# FPGA.net
KiCad netlist of a schematic drawn in Altium Designer
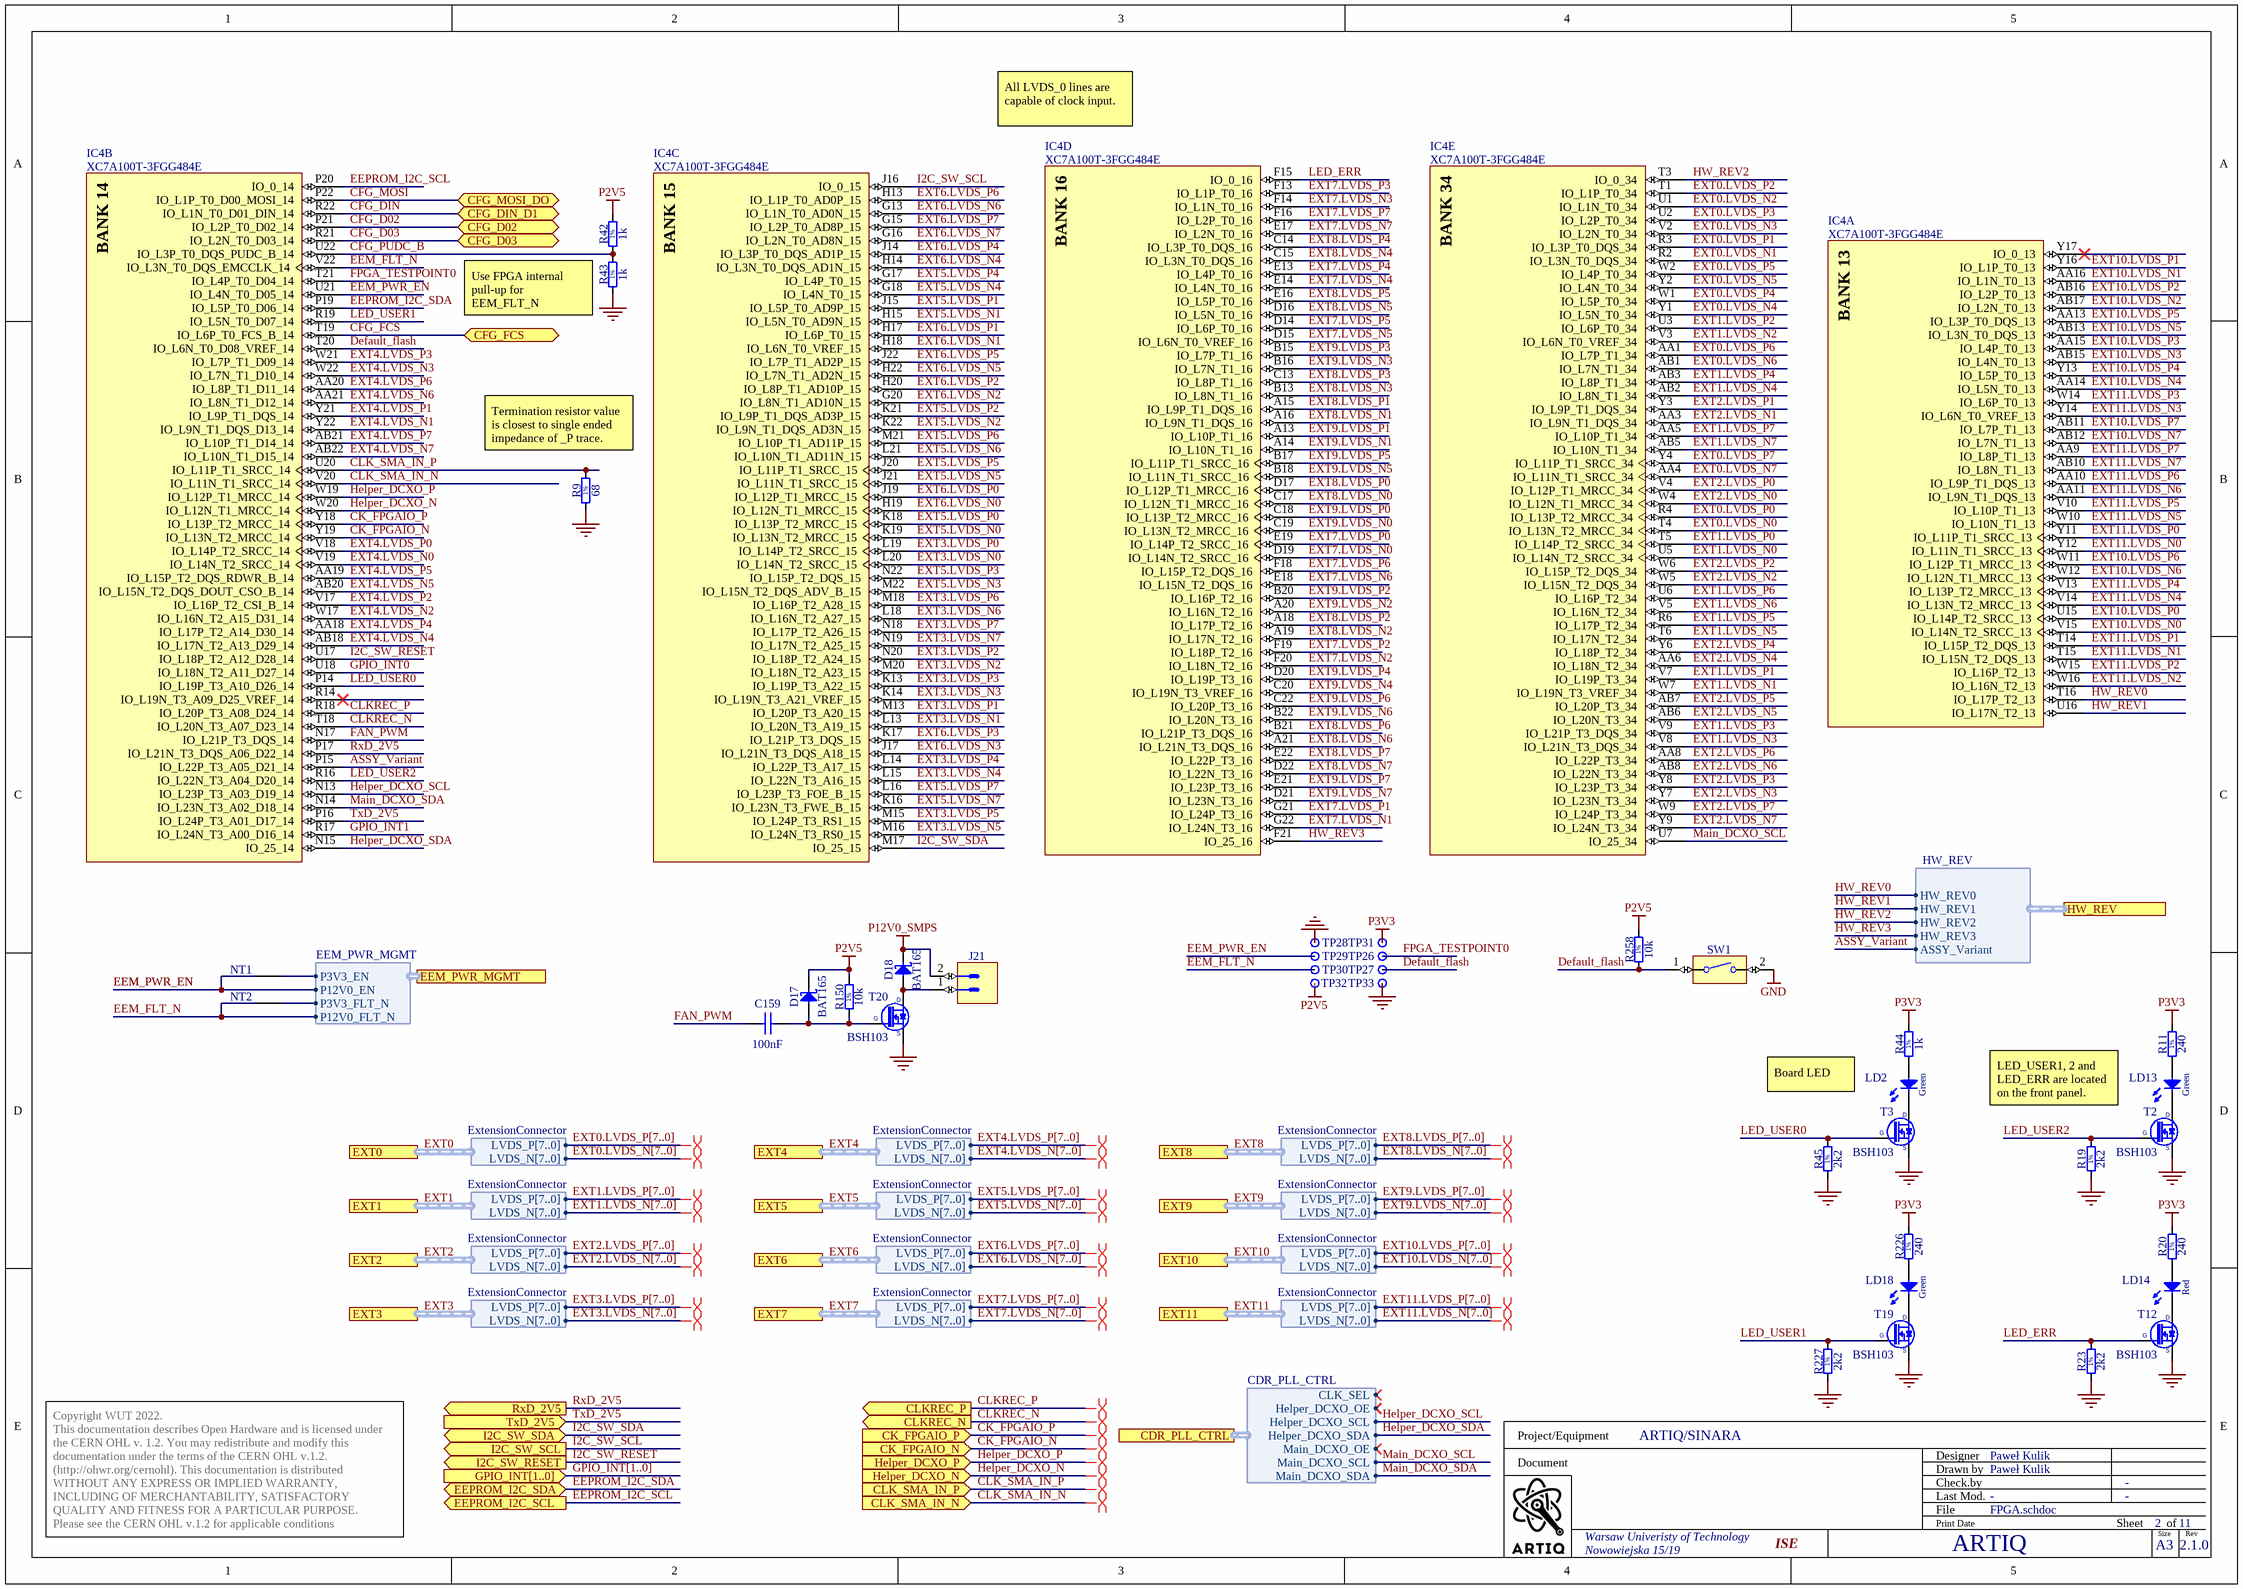
[diagram p0: FPGA.schdoc]

(export (version "E")
  (design (tool "Eeschema 10.0.6"))
  (components
    (comp (ref "C159")
      (value "100nF")
      (footprint "CAPC0603X33N")
      (description "Non-polarised capacitor")
      (fields
        (field (name "PART NUMBER") "CC0201_100NF_6.3V_10%_X5R")
        (field (name "VOLTAGE") "6.3V")
        (field (name "AUTHOR") "CERN DEM JLC")
      )
      (libsource (lib "Capacitors") (part "Capacitor - non polarized"))
    )
    (comp (ref "D17")
      (value "BAT165")
      (footprint "SOD2512X110N")
      (description "Schottky Diode")
      (fields
        (field (name "VOLTAGE") "40V")
        (field (name "POWER") "750mA")
        (field (name "AUTHOR") "CERN DEM JLC")
      )
      (libsource (lib "ICs And Semiconductors") (part "Diode Schottky"))
    )
    (comp (ref "D18")
      (value "BAT165")
      (footprint "SOD2512X110N")
      (description "Schottky Diode")
      (fields
        (field (name "VOLTAGE") "40V")
        (field (name "POWER") "750mA")
        (field (name "AUTHOR") "CERN DEM JLC")
      )
      (libsource (lib "ICs And Semiconductors") (part "Diode Schottky"))
    )
    (comp (ref "IC4")
      (value "XC7A100T-3FGG484E")
      (footprint "BGA484C100P22X22_2300X2300X260")
      (fields (field (name "MANUFACTURER") "XILINX") (field (name "AUTHOR") "CERN DEM BC"))
      (libsource (lib "ICs And Semiconductors") (part "XC7A100T-3FGG484E"))
    )
    (comp (ref "J21")
      (value "KK®")
      (footprint "MOLEX_22-27-2021")
      (description "Connector 2 Male")
      (fields
        (field (name "PART NUMBER") "MOLEX_22-27-2021")
        (field (name "MANUFACTURER") "MOLEX")
        (field (name "AUTHOR") "CERN DEM JLC")
      )
      (libsource (lib "Connectors") (part "Connector 2 Male"))
    )
    (comp (ref "LD2")
      (value "Green")
      (footprint "LED_KINGBRIGHT_KPH-1608CGCK")
      (description "LED Green 1C 2A")
      (fields
        (field (name "MANUFACTURER PART NUMBER") "KPH-1608CGCK")
        (field (name "PART NUMBER") "LED_KINGBRIGHT_KPH-1608CGCK")
        (field (name "AUTHOR") "CERN DEM JLC")
      )
      (libsource (lib "ICs And Semiconductors") (part "LED Green 1C 2A"))
    )
    (comp (ref "LD13")
      (value "Green")
      (footprint "LED_AVAGO_HSME-C120")
      (description "LED Green 1C 2A")
      (fields
        (field (name "MANUFACTURER PART NUMBER") "HSME-C120")
        (field (name "PART NUMBER") "LED_AVAGO_HSME-C120")
        (field (name "AUTHOR") "CERN DEM JMW")
      )
      (libsource (lib "ICs And Semiconductors") (part "LED Green 1C 2A"))
    )
    (comp (ref "LD14")
      (value "Red")
      (footprint "LED_AVAGO_HSMC-C120")
      (description "LED Red 1C 2A")
      (fields
        (field (name "MANUFACTURER PART NUMBER") "HSMC-C120")
        (field (name "PART NUMBER") "LED_AVAGO_HSMC-C120")
        (field (name "AUTHOR") "CERN DEM JMW")
      )
      (libsource (lib "ICs And Semiconductors") (part "LED Red 1C 2A"))
    )
    (comp (ref "LD18")
      (value "Green")
      (footprint "LED_AVAGO_HSME-C120")
      (description "LED Green 1C 2A")
      (fields
        (field (name "MANUFACTURER PART NUMBER") "HSME-C120")
        (field (name "PART NUMBER") "LED_AVAGO_HSME-C120")
        (field (name "AUTHOR") "CERN DEM JMW")
      )
      (libsource (lib "ICs And Semiconductors") (part "LED Green 1C 2A"))
    )
    (comp (ref "NT1")
      (value "Net Tie")
      (footprint "Net Tie")
      (fields (field (name "AUTHOR") "CERN DEM JLC"))
      (libsource (lib "Thermostat") (part "Net Tie"))
    )
    (comp (ref "NT2")
      (value "Net Tie")
      (footprint "Net Tie")
      (fields (field (name "AUTHOR") "CERN DEM JLC"))
      (libsource (lib "Thermostat") (part "Net Tie"))
    )
    (comp (ref "R9")
      (value "68")
      (footprint "RESC1005X40N")
      (description "Resistor - 1%")
      (fields
        (field (name "PART NUMBER") "R0402_68R_1%_0.0625W_100PPM")
        (field (name "POWER") "0.0625W")
        (field (name "AUTHOR") "CERN DEM JLC")
      )
      (libsource (lib "Resistors") (part "Resistor - 1%"))
    )
    (comp (ref "R11")
      (value "240")
      (footprint "RESC1005X40N")
      (description "Resistor - 1%")
      (fields
        (field (name "PART NUMBER") "R0402_240R_1%_0.0625W_100PPM")
        (field (name "POWER") "0.0625W")
        (field (name "AUTHOR") "CERN DEM JLC")
      )
      (libsource (lib "Resistors") (part "Resistor - 1%"))
    )
    (comp (ref "R19")
      (value "2k2")
      (footprint "RESC1005X40N")
      (description "Resistor - 1%")
      (fields
        (field (name "PART NUMBER") "R0402_2K2_1%_0.0625W_100PPM")
        (field (name "POWER") "0.0625W")
        (field (name "AUTHOR") "CERN DEM JLC")
      )
      (libsource (lib "Resistors") (part "Resistor - 1%"))
    )
    (comp (ref "R20")
      (value "240")
      (footprint "RESC1005X40N")
      (description "Resistor - 1%")
      (fields
        (field (name "PART NUMBER") "R0402_240R_1%_0.0625W_100PPM")
        (field (name "POWER") "0.0625W")
        (field (name "AUTHOR") "CERN DEM JLC")
      )
      (libsource (lib "Resistors") (part "Resistor - 1%"))
    )
    (comp (ref "R23")
      (value "2k2")
      (footprint "RESC1005X40N")
      (description "Resistor - 1%")
      (fields
        (field (name "PART NUMBER") "R0402_2K2_1%_0.0625W_100PPM")
        (field (name "POWER") "0.0625W")
        (field (name "AUTHOR") "CERN DEM JLC")
      )
      (libsource (lib "Resistors") (part "Resistor - 1%"))
    )
    (comp (ref "R42")
      (value "1k")
      (footprint "RESC1005X40N")
      (description "Resistor - 1%")
      (fields
        (field (name "PART NUMBER") "R0402_1K_1%_0.0625W_100PPM")
        (field (name "POWER") "0.0625W")
        (field (name "AUTHOR") "CERN DEM JLC")
      )
      (libsource (lib "Resistors") (part "Resistor - 1%"))
    )
    (comp (ref "R43")
      (value "1k")
      (footprint "RESC1005X40N")
      (description "Resistor - 1%")
      (fields
        (field (name "PART NUMBER") "R0402_1K_1%_0.0625W_100PPM")
        (field (name "POWER") "0.0625W")
        (field (name "AUTHOR") "CERN DEM JLC")
      )
      (libsource (lib "Resistors") (part "Resistor - 1%"))
    )
    (comp (ref "R44")
      (value "1k")
      (footprint "RESC1005X40N")
      (description "Resistor - 1%")
      (fields
        (field (name "PART NUMBER") "R0402_1K_1%_0.0625W_100PPM")
        (field (name "POWER") "0.0625W")
        (field (name "AUTHOR") "CERN DEM JLC")
      )
      (libsource (lib "Resistors") (part "Resistor - 1%"))
    )
    (comp (ref "R45")
      (value "2k2")
      (footprint "RESC1005X40N")
      (description "Resistor - 1%")
      (fields
        (field (name "PART NUMBER") "R0402_2K2_1%_0.0625W_100PPM")
        (field (name "POWER") "0.0625W")
        (field (name "AUTHOR") "CERN DEM JLC")
      )
      (libsource (lib "Resistors") (part "Resistor - 1%"))
    )
    (comp (ref "R150")
      (value "10k")
      (footprint "RESC1005X40N")
      (description "Resistor - 1%")
      (fields
        (field (name "PART NUMBER") "R0402_10K_1%_0.0625W_100PPM")
        (field (name "POWER") "0.0625W")
        (field (name "AUTHOR") "CERN DEM JLC")
      )
      (libsource (lib "Resistors") (part "Resistor - 1%"))
    )
    (comp (ref "R226")
      (value "240")
      (footprint "RESC1005X40N")
      (description "Resistor - 1%")
      (fields
        (field (name "PART NUMBER") "R0402_240R_1%_0.0625W_100PPM")
        (field (name "POWER") "0.0625W")
        (field (name "AUTHOR") "CERN DEM JLC")
      )
      (libsource (lib "Resistors") (part "Resistor - 1%"))
    )
    (comp (ref "R227")
      (value "2k2")
      (footprint "RESC1005X40N")
      (description "Resistor - 1%")
      (fields
        (field (name "PART NUMBER") "R0402_2K2_1%_0.0625W_100PPM")
        (field (name "POWER") "0.0625W")
        (field (name "AUTHOR") "CERN DEM JLC")
      )
      (libsource (lib "Resistors") (part "Resistor - 1%"))
    )
    (comp (ref "R258")
      (value "10k")
      (footprint "RESC1005X40N")
      (description "Resistor - 1%")
      (fields
        (field (name "PART NUMBER") "R0402_10K_1%_0.0625W_100PPM")
        (field (name "POWER") "0.0625W")
        (field (name "AUTHOR") "CERN DEM JLC")
      )
      (libsource (lib "Resistors") (part "Resistor - 1%"))
    )
    (comp (ref "SW1")
      (value "Switch")
      (footprint "SW_OMRON_B3U-3000PM")
      (description "1 Ways SPST DIP Switch")
      (fields
        (field (name "PART NUMBER") "SW_OMRON_B3U-3000PM")
        (field (name "MANUFACTURER") "OMRON")
        (field (name "AUTHOR") "CERN DEM HF")
      )
      (libsource (lib "Eletro-mechanical") (part "SW 1x SPST DIP Switch"))
    )
    (comp (ref "T2")
      (value "BSH103")
      (footprint "SOT95P230X110-3N")
      (description "N-CHANNEL MOSFET WITH DIODE")
      (fields (field (name "MANUFACTURER") "NEXPERIA") (field (name "AUTHOR") "CERN DEM JLC"))
      (libsource (lib "ICs And Semiconductors") (part "N-MOSFET-D 1G 2S 3D"))
    )
    (comp (ref "T3")
      (value "BSH103")
      (footprint "SOT95P230X110-3N")
      (description "N-CHANNEL MOSFET WITH DIODE")
      (fields (field (name "MANUFACTURER") "NEXPERIA") (field (name "AUTHOR") "CERN DEM JLC"))
      (libsource (lib "ICs And Semiconductors") (part "N-MOSFET-D 1G 2S 3D"))
    )
    (comp (ref "T12")
      (value "BSH103")
      (footprint "SOT95P230X110-3N")
      (description "N-CHANNEL MOSFET WITH DIODE")
      (fields (field (name "MANUFACTURER") "NEXPERIA") (field (name "AUTHOR") "CERN DEM JLC"))
      (libsource (lib "ICs And Semiconductors") (part "N-MOSFET-D 1G 2S 3D"))
    )
    (comp (ref "T19")
      (value "BSH103")
      (footprint "SOT95P230X110-3N")
      (description "N-CHANNEL MOSFET WITH DIODE")
      (fields (field (name "MANUFACTURER") "NEXPERIA") (field (name "AUTHOR") "CERN DEM JLC"))
      (libsource (lib "ICs And Semiconductors") (part "N-MOSFET-D 1G 2S 3D"))
    )
    (comp (ref "T20")
      (value "BSH103")
      (footprint "SOT95P230X110-3N")
      (description "N-CHANNEL MOSFET WITH DIODE")
      (fields (field (name "MANUFACTURER") "NEXPERIA") (field (name "AUTHOR") "CERN DEM JLC"))
      (libsource (lib "ICs And Semiconductors") (part "N-MOSFET-D 1G 2S 3D"))
    )
    (comp (ref "TP26")
      (value "Plated Hole")
      (footprint "c170h100")
      (description "Single Terminal Socket")
      (fields (field (name "PART NUMBER") "PLATED_HOLE1.0_PAD1.7") (field (name "AUTHOR") "CERN DEM JLC"))
      (libsource (lib "Eletro-mechanical") (part "Single Terminal Socket"))
    )
    (comp (ref "TP27")
      (value "Plated Hole")
      (footprint "c170h100")
      (description "Single Terminal Socket")
      (fields (field (name "PART NUMBER") "PLATED_HOLE1.0_PAD1.7") (field (name "AUTHOR") "CERN DEM JLC"))
      (libsource (lib "Eletro-mechanical") (part "Single Terminal Socket"))
    )
    (comp (ref "TP28")
      (value "Plated Hole")
      (footprint "c170h100")
      (description "Single Terminal Socket")
      (fields (field (name "PART NUMBER") "PLATED_HOLE1.0_PAD1.7") (field (name "AUTHOR") "CERN DEM JLC"))
      (libsource (lib "Eletro-mechanical") (part "Single Terminal Socket"))
    )
    (comp (ref "TP29")
      (value "Plated Hole")
      (footprint "c170h100")
      (description "Single Terminal Socket")
      (fields (field (name "PART NUMBER") "PLATED_HOLE1.0_PAD1.7") (field (name "AUTHOR") "CERN DEM JLC"))
      (libsource (lib "Eletro-mechanical") (part "Single Terminal Socket"))
    )
    (comp (ref "TP30")
      (value "Plated Hole")
      (footprint "c170h100")
      (description "Single Terminal Socket")
      (fields (field (name "PART NUMBER") "PLATED_HOLE1.0_PAD1.7") (field (name "AUTHOR") "CERN DEM JLC"))
      (libsource (lib "Eletro-mechanical") (part "Single Terminal Socket"))
    )
    (comp (ref "TP31")
      (value "Plated Hole")
      (footprint "c170h100")
      (description "Single Terminal Socket")
      (fields (field (name "PART NUMBER") "PLATED_HOLE1.0_PAD1.7") (field (name "AUTHOR") "CERN DEM JLC"))
      (libsource (lib "Eletro-mechanical") (part "Single Terminal Socket"))
    )
    (comp (ref "TP32")
      (value "Plated Hole")
      (footprint "c170h100")
      (description "Single Terminal Socket")
      (fields (field (name "PART NUMBER") "PLATED_HOLE1.0_PAD1.7") (field (name "AUTHOR") "CERN DEM JLC"))
      (libsource (lib "Eletro-mechanical") (part "Single Terminal Socket"))
    )
    (comp (ref "TP33")
      (value "Plated Hole")
      (footprint "c170h100")
      (description "Single Terminal Socket")
      (fields (field (name "PART NUMBER") "PLATED_HOLE1.0_PAD1.7") (field (name "AUTHOR") "CERN DEM JLC"))
      (libsource (lib "Eletro-mechanical") (part "Single Terminal Socket"))
    )
  )
  (nets
    (net (code "16") (name "/ASSY_Variant") (class "Default")
      (node (ref "IC4") (pin "P15") (pinfunction "IO_L22P_T3_A05_D21_14_P15") (pintype "bidirectional"))
    )
    (net (code "17") (name "/CFG_D02") (class "Default")
      (node (ref "IC4") (pin "P21") (pinfunction "IO_L2P_T0_D02_14_P21") (pintype "bidirectional"))
    )
    (net (code "18") (name "/CFG_D03") (class "Default")
      (node (ref "IC4") (pin "R21") (pinfunction "IO_L2N_T0_D03_14_R21") (pintype "bidirectional"))
    )
    (net (code "19") (name "/CFG_DIN") (class "Default")
      (node (ref "IC4") (pin "R22") (pinfunction "IO_L1N_T0_D01_DIN_14_R22") (pintype "bidirectional"))
    )
    (net (code "20") (name "/CFG_FCS") (class "Default")
      (node (ref "IC4") (pin "T19") (pinfunction "IO_L6P_T0_FCS_B_14_T19") (pintype "bidirectional"))
    )
    (net (code "21") (name "/CFG_MOSI") (class "Default")
      (node (ref "IC4") (pin "P22") (pinfunction "IO_L1P_T0_D00_MOSI_14_P22") (pintype "bidirectional"))
    )
    (net (code "22") (name "/CFG_PUDC_B") (class "Default")
      (node (ref "IC4") (pin "U22") (pinfunction "IO_L3P_T0_DQS_PUDC_B_14_U22") (pintype "bidirectional"))
      (node (ref "R42") (pin "1") (pinfunction "1_1") (pintype "passive"))
      (node (ref "R43") (pin "2") (pinfunction "2_2") (pintype "passive"))
    )
    (net (code "23") (name "/CK_FPGAIO_N") (class "Default")
      (node (ref "IC4") (pin "Y19") (pinfunction "IO_L13N_T2_MRCC_14_Y19") (pintype "bidirectional"))
    )
    (net (code "24") (name "/CK_FPGAIO_P") (class "Default")
      (node (ref "IC4") (pin "Y18") (pinfunction "IO_L13P_T2_MRCC_14_Y18") (pintype "bidirectional"))
    )
    (net (code "25") (name "/CLKREC_N") (class "Default")
      (node (ref "IC4") (pin "T18") (pinfunction "IO_L20N_T3_A07_D23_14_T18") (pintype "bidirectional"))
    )
    (net (code "26") (name "/CLKREC_P") (class "Default")
      (node (ref "IC4") (pin "R18") (pinfunction "IO_L20P_T3_A08_D24_14_R18") (pintype "bidirectional"))
    )
    (net (code "27") (name "/CLK_SMA_IN_N") (class "Default")
      (node (ref "IC4") (pin "V20") (pinfunction "IO_L11N_T1_SRCC_14_V20") (pintype "bidirectional"))
    )
    (net (code "28") (name "/CLK_SMA_IN_P") (class "Default")
      (node (ref "IC4") (pin "U20") (pinfunction "IO_L11P_T1_SRCC_14_U20") (pintype "bidirectional"))
      (node (ref "R9") (pin "2") (pinfunction "2_2") (pintype "passive"))
    )
    (net (code "29") (name "/Default_flash") (class "Default")
      (node (ref "IC4") (pin "T20") (pinfunction "IO_L6N_T0_D08_VREF_14_T20") (pintype "bidirectional"))
      (node (ref "R258") (pin "1") (pinfunction "1_1") (pintype "passive"))
      (node (ref "SW1") (pin "1") (pinfunction "1_1") (pintype "bidirectional"))
      (node (ref "TP27") (pin "1") (pinfunction "1_1") (pintype "bidirectional"))
    )
    (net (code "30") (name "/EEM_FLT_N") (class "Default")
      (node (ref "IC4") (pin "V22") (pinfunction "IO_L3N_T0_DQS_EMCCLK_14_V22") (pintype "bidirectional"))
      (node (ref "NT2") (pin "1") (pinfunction "1_1") (pintype "bidirectional"))
      (node (ref "TP30") (pin "1") (pinfunction "1_1") (pintype "bidirectional"))
    )
    (net (code "31") (name "/EEM_PWR_EN") (class "Default")
      (node (ref "IC4") (pin "U21") (pinfunction "IO_L4N_T0_D05_14_U21") (pintype "bidirectional"))
      (node (ref "NT1") (pin "1") (pinfunction "1_1") (pintype "bidirectional"))
      (node (ref "TP29") (pin "1") (pinfunction "1_1") (pintype "bidirectional"))
    )
    (net (code "32") (name "/EEPROM_I2C_SCL") (class "Default")
      (node (ref "IC4") (pin "P20") (pinfunction "IO_0_14_P20") (pintype "bidirectional"))
    )
    (net (code "33") (name "/EEPROM_I2C_SDA") (class "Default")
      (node (ref "IC4") (pin "P19") (pinfunction "IO_L5P_T0_D06_14_P19") (pintype "bidirectional"))
    )
    (net (code "34") (name "/EXT0.LVDS_N0") (class "Default")
      (node (ref "IC4") (pin "T4") (pinfunction "IO_L13N_T2_MRCC_34_T4") (pintype "bidirectional"))
    )
    (net (code "35") (name "/EXT0.LVDS_N1") (class "Default")
      (node (ref "IC4") (pin "R2") (pinfunction "IO_L3N_T0_DQS_34_R2") (pintype "bidirectional"))
    )
    (net (code "36") (name "/EXT0.LVDS_N2") (class "Default")
      (node (ref "IC4") (pin "U1") (pinfunction "IO_L1N_T0_34_U1") (pintype "bidirectional"))
    )
    (net (code "37") (name "/EXT0.LVDS_N3") (class "Default")
      (node (ref "IC4") (pin "V2") (pinfunction "IO_L2N_T0_34_V2") (pintype "bidirectional"))
    )
    (net (code "38") (name "/EXT0.LVDS_N4") (class "Default")
      (node (ref "IC4") (pin "Y1") (pinfunction "IO_L5N_T0_34_Y1") (pintype "bidirectional"))
    )
    (net (code "39") (name "/EXT0.LVDS_N5") (class "Default")
      (node (ref "IC4") (pin "Y2") (pinfunction "IO_L4N_T0_34_Y2") (pintype "bidirectional"))
    )
    (net (code "40") (name "/EXT0.LVDS_N6") (class "Default")
      (node (ref "IC4") (pin "AB1") (pinfunction "IO_L7N_T1_34_AB1") (pintype "bidirectional"))
    )
    (net (code "41") (name "/EXT0.LVDS_N7") (class "Default")
      (node (ref "IC4") (pin "AA4") (pinfunction "IO_L11N_T1_SRCC_34_AA4") (pintype "bidirectional"))
    )
    (net (code "43") (name "/EXT0.LVDS_P0") (class "Default")
      (node (ref "IC4") (pin "R4") (pinfunction "IO_L13P_T2_MRCC_34_R4") (pintype "bidirectional"))
    )
    (net (code "44") (name "/EXT0.LVDS_P1") (class "Default")
      (node (ref "IC4") (pin "R3") (pinfunction "IO_L3P_T0_DQS_34_R3") (pintype "bidirectional"))
    )
    (net (code "45") (name "/EXT0.LVDS_P2") (class "Default")
      (node (ref "IC4") (pin "T1") (pinfunction "IO_L1P_T0_34_T1") (pintype "bidirectional"))
    )
    (net (code "46") (name "/EXT0.LVDS_P3") (class "Default")
      (node (ref "IC4") (pin "U2") (pinfunction "IO_L2P_T0_34_U2") (pintype "bidirectional"))
    )
    (net (code "47") (name "/EXT0.LVDS_P4") (class "Default")
      (node (ref "IC4") (pin "W1") (pinfunction "IO_L5P_T0_34_W1") (pintype "bidirectional"))
    )
    (net (code "48") (name "/EXT0.LVDS_P5") (class "Default")
      (node (ref "IC4") (pin "W2") (pinfunction "IO_L4P_T0_34_W2") (pintype "bidirectional"))
    )
    (net (code "49") (name "/EXT0.LVDS_P6") (class "Default")
      (node (ref "IC4") (pin "AA1") (pinfunction "IO_L7P_T1_34_AA1") (pintype "bidirectional"))
    )
    (net (code "50") (name "/EXT0.LVDS_P7") (class "Default")
      (node (ref "IC4") (pin "Y4") (pinfunction "IO_L11P_T1_SRCC_34_Y4") (pintype "bidirectional"))
    )
    (net (code "51") (name "/EXT1.LVDS_N0") (class "Default")
      (node (ref "IC4") (pin "U5") (pinfunction "IO_L14N_T2_SRCC_34_U5") (pintype "bidirectional"))
    )
    (net (code "52") (name "/EXT1.LVDS_N1") (class "Default")
      (node (ref "IC4") (pin "W7") (pinfunction "IO_L19N_T3_VREF_34_W7") (pintype "bidirectional"))
    )
    (net (code "53") (name "/EXT1.LVDS_N2") (class "Default")
      (node (ref "IC4") (pin "V3") (pinfunction "IO_L6N_T0_VREF_34_V3") (pintype "bidirectional"))
    )
    (net (code "54") (name "/EXT1.LVDS_N3") (class "Default")
      (node (ref "IC4") (pin "V8") (pinfunction "IO_L21N_T3_DQS_34_V8") (pintype "bidirectional"))
    )
    (net (code "55") (name "/EXT1.LVDS_N4") (class "Default")
      (node (ref "IC4") (pin "AB2") (pinfunction "IO_L8N_T1_34_AB2") (pintype "bidirectional"))
    )
    (net (code "56") (name "/EXT1.LVDS_N5") (class "Default")
      (node (ref "IC4") (pin "T6") (pinfunction "IO_L17N_T2_34_T6") (pintype "bidirectional"))
    )
    (net (code "57") (name "/EXT1.LVDS_N6") (class "Default")
      (node (ref "IC4") (pin "V5") (pinfunction "IO_L16N_T2_34_V5") (pintype "bidirectional"))
    )
    (net (code "58") (name "/EXT1.LVDS_N7") (class "Default")
      (node (ref "IC4") (pin "AB5") (pinfunction "IO_L10N_T1_34_AB5") (pintype "bidirectional"))
    )
    (net (code "60") (name "/EXT1.LVDS_P0") (class "Default")
      (node (ref "IC4") (pin "T5") (pinfunction "IO_L14P_T2_SRCC_34_T5") (pintype "bidirectional"))
    )
    (net (code "61") (name "/EXT1.LVDS_P1") (class "Default")
      (node (ref "IC4") (pin "V7") (pinfunction "IO_L19P_T3_34_V7") (pintype "bidirectional"))
    )
    (net (code "62") (name "/EXT1.LVDS_P2") (class "Default")
      (node (ref "IC4") (pin "U3") (pinfunction "IO_L6P_T0_34_U3") (pintype "bidirectional"))
    )
    (net (code "63") (name "/EXT1.LVDS_P3") (class "Default")
      (node (ref "IC4") (pin "V9") (pinfunction "IO_L21P_T3_DQS_34_V9") (pintype "bidirectional"))
    )
    (net (code "64") (name "/EXT1.LVDS_P4") (class "Default")
      (node (ref "IC4") (pin "AB3") (pinfunction "IO_L8P_T1_34_AB3") (pintype "bidirectional"))
    )
    (net (code "65") (name "/EXT1.LVDS_P5") (class "Default")
      (node (ref "IC4") (pin "R6") (pinfunction "IO_L17P_T2_34_R6") (pintype "bidirectional"))
    )
    (net (code "66") (name "/EXT1.LVDS_P6") (class "Default")
      (node (ref "IC4") (pin "U6") (pinfunction "IO_L16P_T2_34_U6") (pintype "bidirectional"))
    )
    (net (code "67") (name "/EXT1.LVDS_P7") (class "Default")
      (node (ref "IC4") (pin "AA5") (pinfunction "IO_L10P_T1_34_AA5") (pintype "bidirectional"))
    )
    (net (code "70") (name "/EXT2.LVDS_N0") (class "Default")
      (node (ref "IC4") (pin "W4") (pinfunction "IO_L12N_T1_MRCC_34_W4") (pintype "bidirectional"))
    )
    (net (code "71") (name "/EXT2.LVDS_N1") (class "Default")
      (node (ref "IC4") (pin "AA3") (pinfunction "IO_L9N_T1_DQS_34_AA3") (pintype "bidirectional"))
    )
    (net (code "72") (name "/EXT2.LVDS_N2") (class "Default")
      (node (ref "IC4") (pin "W5") (pinfunction "IO_L15N_T2_DQS_34_W5") (pintype "bidirectional"))
    )
    (net (code "73") (name "/EXT2.LVDS_N3") (class "Default")
      (node (ref "IC4") (pin "Y7") (pinfunction "IO_L23N_T3_34_Y7") (pintype "bidirectional"))
    )
    (net (code "74") (name "/EXT2.LVDS_N4") (class "Default")
      (node (ref "IC4") (pin "AA6") (pinfunction "IO_L18N_T2_34_AA6") (pintype "bidirectional"))
    )
    (net (code "75") (name "/EXT2.LVDS_N5") (class "Default")
      (node (ref "IC4") (pin "AB6") (pinfunction "IO_L20N_T3_34_AB6") (pintype "bidirectional"))
    )
    (net (code "76") (name "/EXT2.LVDS_N6") (class "Default")
      (node (ref "IC4") (pin "AB8") (pinfunction "IO_L22N_T3_34_AB8") (pintype "bidirectional"))
    )
    (net (code "77") (name "/EXT2.LVDS_N7") (class "Default")
      (node (ref "IC4") (pin "Y9") (pinfunction "IO_L24N_T3_34_Y9") (pintype "bidirectional"))
    )
    (net (code "79") (name "/EXT2.LVDS_P0") (class "Default")
      (node (ref "IC4") (pin "V4") (pinfunction "IO_L12P_T1_MRCC_34_V4") (pintype "bidirectional"))
    )
    (net (code "80") (name "/EXT2.LVDS_P1") (class "Default")
      (node (ref "IC4") (pin "Y3") (pinfunction "IO_L9P_T1_DQS_34_Y3") (pintype "bidirectional"))
    )
    (net (code "81") (name "/EXT2.LVDS_P2") (class "Default")
      (node (ref "IC4") (pin "W6") (pinfunction "IO_L15P_T2_DQS_34_W6") (pintype "bidirectional"))
    )
    (net (code "82") (name "/EXT2.LVDS_P3") (class "Default")
      (node (ref "IC4") (pin "Y8") (pinfunction "IO_L23P_T3_34_Y8") (pintype "bidirectional"))
    )
    (net (code "83") (name "/EXT2.LVDS_P4") (class "Default")
      (node (ref "IC4") (pin "Y6") (pinfunction "IO_L18P_T2_34_Y6") (pintype "bidirectional"))
    )
    (net (code "84") (name "/EXT2.LVDS_P5") (class "Default")
      (node (ref "IC4") (pin "AB7") (pinfunction "IO_L20P_T3_34_AB7") (pintype "bidirectional"))
    )
    (net (code "85") (name "/EXT2.LVDS_P6") (class "Default")
      (node (ref "IC4") (pin "AA8") (pinfunction "IO_L22P_T3_34_AA8") (pintype "bidirectional"))
    )
    (net (code "86") (name "/EXT2.LVDS_P7") (class "Default")
      (node (ref "IC4") (pin "W9") (pinfunction "IO_L24P_T3_34_W9") (pintype "bidirectional"))
    )
    (net (code "87") (name "/EXT3.LVDS_N0") (class "Default")
      (node (ref "IC4") (pin "L20") (pinfunction "IO_L14N_T2_SRCC_15_L20") (pintype "bidirectional"))
    )
    (net (code "88") (name "/EXT3.LVDS_N1") (class "Default")
      (node (ref "IC4") (pin "L13") (pinfunction "IO_L20N_T3_A19_15_L13") (pintype "bidirectional"))
    )
    (net (code "89") (name "/EXT3.LVDS_N2") (class "Default")
      (node (ref "IC4") (pin "M20") (pinfunction "IO_L18N_T2_A23_15_M20") (pintype "bidirectional"))
    )
    (net (code "90") (name "/EXT3.LVDS_N3") (class "Default")
      (node (ref "IC4") (pin "K14") (pinfunction "IO_L19N_T3_A21_VREF_15_K14") (pintype "bidirectional"))
    )
    (net (code "91") (name "/EXT3.LVDS_N4") (class "Default")
      (node (ref "IC4") (pin "L15") (pinfunction "IO_L22N_T3_A16_15_L15") (pintype "bidirectional"))
    )
    (net (code "92") (name "/EXT3.LVDS_N5") (class "Default")
      (node (ref "IC4") (pin "M16") (pinfunction "IO_L24N_T3_RS0_15_M16") (pintype "bidirectional"))
    )
    (net (code "93") (name "/EXT3.LVDS_N6") (class "Default")
      (node (ref "IC4") (pin "L18") (pinfunction "IO_L16N_T2_A27_15_L18") (pintype "bidirectional"))
    )
    (net (code "94") (name "/EXT3.LVDS_N7") (class "Default")
      (node (ref "IC4") (pin "N19") (pinfunction "IO_L17N_T2_A25_15_N19") (pintype "bidirectional"))
    )
    (net (code "96") (name "/EXT3.LVDS_P0") (class "Default")
      (node (ref "IC4") (pin "L19") (pinfunction "IO_L14P_T2_SRCC_15_L19") (pintype "bidirectional"))
    )
    (net (code "97") (name "/EXT3.LVDS_P1") (class "Default")
      (node (ref "IC4") (pin "M13") (pinfunction "IO_L20P_T3_A20_15_M13") (pintype "bidirectional"))
    )
    (net (code "98") (name "/EXT3.LVDS_P2") (class "Default")
      (node (ref "IC4") (pin "N20") (pinfunction "IO_L18P_T2_A24_15_N20") (pintype "bidirectional"))
    )
    (net (code "99") (name "/EXT3.LVDS_P3") (class "Default")
      (node (ref "IC4") (pin "K13") (pinfunction "IO_L19P_T3_A22_15_K13") (pintype "bidirectional"))
    )
    (net (code "100") (name "/EXT3.LVDS_P4") (class "Default")
      (node (ref "IC4") (pin "L14") (pinfunction "IO_L22P_T3_A17_15_L14") (pintype "bidirectional"))
    )
    (net (code "101") (name "/EXT3.LVDS_P5") (class "Default")
      (node (ref "IC4") (pin "M15") (pinfunction "IO_L24P_T3_RS1_15_M15") (pintype "bidirectional"))
    )
    (net (code "102") (name "/EXT3.LVDS_P6") (class "Default")
      (node (ref "IC4") (pin "M18") (pinfunction "IO_L16P_T2_A28_15_M18") (pintype "bidirectional"))
    )
    (net (code "103") (name "/EXT3.LVDS_P7") (class "Default")
      (node (ref "IC4") (pin "N18") (pinfunction "IO_L17P_T2_A26_15_N18") (pintype "bidirectional"))
    )
    (net (code "104") (name "/EXT4.LVDS_N0") (class "Default")
      (node (ref "IC4") (pin "V19") (pinfunction "IO_L14N_T2_SRCC_14_V19") (pintype "bidirectional"))
    )
    (net (code "105") (name "/EXT4.LVDS_N1") (class "Default")
      (node (ref "IC4") (pin "Y22") (pinfunction "IO_L9N_T1_DQS_D13_14_Y22") (pintype "bidirectional"))
    )
    (net (code "106") (name "/EXT4.LVDS_N2") (class "Default")
      (node (ref "IC4") (pin "W17") (pinfunction "IO_L16N_T2_A15_D31_14_W17") (pintype "bidirectional"))
    )
    (net (code "107") (name "/EXT4.LVDS_N3") (class "Default")
      (node (ref "IC4") (pin "W22") (pinfunction "IO_L7N_T1_D10_14_W22") (pintype "bidirectional"))
    )
    (net (code "108") (name "/EXT4.LVDS_N4") (class "Default")
      (node (ref "IC4") (pin "AB18") (pinfunction "IO_L17N_T2_A13_D29_14_AB18") (pintype "bidirectional"))
    )
    (net (code "109") (name "/EXT4.LVDS_N5") (class "Default")
      (node (ref "IC4") (pin "AB20") (pinfunction "IO_L15N_T2_DQS_DOUT_CSO_B_14_AB20") (pintype "bidirectional"))
    )
    (net (code "110") (name "/EXT4.LVDS_N6") (class "Default")
      (node (ref "IC4") (pin "AA21") (pinfunction "IO_L8N_T1_D12_14_AA21") (pintype "bidirectional"))
    )
    (net (code "111") (name "/EXT4.LVDS_N7") (class "Default")
      (node (ref "IC4") (pin "AB22") (pinfunction "IO_L10N_T1_D15_14_AB22") (pintype "bidirectional"))
    )
    (net (code "113") (name "/EXT4.LVDS_P0") (class "Default")
      (node (ref "IC4") (pin "V18") (pinfunction "IO_L14P_T2_SRCC_14_V18") (pintype "bidirectional"))
    )
    (net (code "114") (name "/EXT4.LVDS_P1") (class "Default")
      (node (ref "IC4") (pin "Y21") (pinfunction "IO_L9P_T1_DQS_14_Y21") (pintype "bidirectional"))
    )
    (net (code "115") (name "/EXT4.LVDS_P2") (class "Default")
      (node (ref "IC4") (pin "V17") (pinfunction "IO_L16P_T2_CSI_B_14_V17") (pintype "bidirectional"))
    )
    (net (code "116") (name "/EXT4.LVDS_P3") (class "Default")
      (node (ref "IC4") (pin "W21") (pinfunction "IO_L7P_T1_D09_14_W21") (pintype "bidirectional"))
    )
    (net (code "117") (name "/EXT4.LVDS_P4") (class "Default")
      (node (ref "IC4") (pin "AA18") (pinfunction "IO_L17P_T2_A14_D30_14_AA18") (pintype "bidirectional"))
    )
    (net (code "118") (name "/EXT4.LVDS_P5") (class "Default")
      (node (ref "IC4") (pin "AA19") (pinfunction "IO_L15P_T2_DQS_RDWR_B_14_AA19") (pintype "bidirectional"))
    )
    (net (code "119") (name "/EXT4.LVDS_P6") (class "Default")
      (node (ref "IC4") (pin "AA20") (pinfunction "IO_L8P_T1_D11_14_AA20") (pintype "bidirectional"))
    )
    (net (code "120") (name "/EXT4.LVDS_P7") (class "Default")
      (node (ref "IC4") (pin "AB21") (pinfunction "IO_L10P_T1_D14_14_AB21") (pintype "bidirectional"))
    )
    (net (code "121") (name "/EXT5.LVDS_N0") (class "Default")
      (node (ref "IC4") (pin "K19") (pinfunction "IO_L13N_T2_MRCC_15_K19") (pintype "bidirectional"))
    )
    (net (code "122") (name "/EXT5.LVDS_N1") (class "Default")
      (node (ref "IC4") (pin "H15") (pinfunction "IO_L5N_T0_AD9N_15_H15") (pintype "bidirectional"))
    )
    (net (code "123") (name "/EXT5.LVDS_N2") (class "Default")
      (node (ref "IC4") (pin "K22") (pinfunction "IO_L9N_T1_DQS_AD3N_15_K22") (pintype "bidirectional"))
    )
    (net (code "124") (name "/EXT5.LVDS_N3") (class "Default")
      (node (ref "IC4") (pin "M22") (pinfunction "IO_L15N_T2_DQS_ADV_B_15_M22") (pintype "bidirectional"))
    )
    (net (code "125") (name "/EXT5.LVDS_N4") (class "Default")
      (node (ref "IC4") (pin "G18") (pinfunction "IO_L4N_T0_15_G18") (pintype "bidirectional"))
    )
    (net (code "126") (name "/EXT5.LVDS_N5") (class "Default")
      (node (ref "IC4") (pin "J21") (pinfunction "IO_L11N_T1_SRCC_15_J21") (pintype "bidirectional"))
    )
    (net (code "127") (name "/EXT5.LVDS_N6") (class "Default")
      (node (ref "IC4") (pin "L21") (pinfunction "IO_L10N_T1_AD11N_15_L21") (pintype "bidirectional"))
    )
    (net (code "128") (name "/EXT5.LVDS_N7") (class "Default")
      (node (ref "IC4") (pin "K16") (pinfunction "IO_L23N_T3_FWE_B_15_K16") (pintype "bidirectional"))
    )
    (net (code "130") (name "/EXT5.LVDS_P0") (class "Default")
      (node (ref "IC4") (pin "K18") (pinfunction "IO_L13P_T2_MRCC_15_K18") (pintype "bidirectional"))
    )
    (net (code "131") (name "/EXT5.LVDS_P1") (class "Default")
      (node (ref "IC4") (pin "J15") (pinfunction "IO_L5P_T0_AD9P_15_J15") (pintype "bidirectional"))
    )
    (net (code "132") (name "/EXT5.LVDS_P2") (class "Default")
      (node (ref "IC4") (pin "K21") (pinfunction "IO_L9P_T1_DQS_AD3P_15_K21") (pintype "bidirectional"))
    )
    (net (code "133") (name "/EXT5.LVDS_P3") (class "Default")
      (node (ref "IC4") (pin "N22") (pinfunction "IO_L15P_T2_DQS_15_N22") (pintype "bidirectional"))
    )
    (net (code "134") (name "/EXT5.LVDS_P4") (class "Default")
      (node (ref "IC4") (pin "G17") (pinfunction "IO_L4P_T0_15_G17") (pintype "bidirectional"))
    )
    (net (code "135") (name "/EXT5.LVDS_P5") (class "Default")
      (node (ref "IC4") (pin "J20") (pinfunction "IO_L11P_T1_SRCC_15_J20") (pintype "bidirectional"))
    )
    (net (code "136") (name "/EXT5.LVDS_P6") (class "Default")
      (node (ref "IC4") (pin "M21") (pinfunction "IO_L10P_T1_AD11P_15_M21") (pintype "bidirectional"))
    )
    (net (code "137") (name "/EXT5.LVDS_P7") (class "Default")
      (node (ref "IC4") (pin "L16") (pinfunction "IO_L23P_T3_FOE_B_15_L16") (pintype "bidirectional"))
    )
    (net (code "140") (name "/EXT6.LVDS_N0") (class "Default")
      (node (ref "IC4") (pin "H19") (pinfunction "IO_L12N_T1_MRCC_15_H19") (pintype "bidirectional"))
    )
    (net (code "141") (name "/EXT6.LVDS_N1") (class "Default")
      (node (ref "IC4") (pin "H18") (pinfunction "IO_L6N_T0_VREF_15_H18") (pintype "bidirectional"))
    )
    (net (code "142") (name "/EXT6.LVDS_N2") (class "Default")
      (node (ref "IC4") (pin "G20") (pinfunction "IO_L8N_T1_AD10N_15_G20") (pintype "bidirectional"))
    )
    (net (code "143") (name "/EXT6.LVDS_N3") (class "Default")
      (node (ref "IC4") (pin "J17") (pinfunction "IO_L21N_T3_DQS_A18_15_J17") (pintype "bidirectional"))
    )
    (net (code "144") (name "/EXT6.LVDS_N4") (class "Default")
      (node (ref "IC4") (pin "H14") (pinfunction "IO_L3N_T0_DQS_AD1N_15_H14") (pintype "bidirectional"))
    )
    (net (code "145") (name "/EXT6.LVDS_N5") (class "Default")
      (node (ref "IC4") (pin "H22") (pinfunction "IO_L7N_T1_AD2N_15_H22") (pintype "bidirectional"))
    )
    (net (code "146") (name "/EXT6.LVDS_N6") (class "Default")
      (node (ref "IC4") (pin "G13") (pinfunction "IO_L1N_T0_AD0N_15_G13") (pintype "bidirectional"))
    )
    (net (code "147") (name "/EXT6.LVDS_N7") (class "Default")
      (node (ref "IC4") (pin "G16") (pinfunction "IO_L2N_T0_AD8N_15_G16") (pintype "bidirectional"))
    )
    (net (code "149") (name "/EXT6.LVDS_P0") (class "Default")
      (node (ref "IC4") (pin "J19") (pinfunction "IO_L12P_T1_MRCC_15_J19") (pintype "bidirectional"))
    )
    (net (code "150") (name "/EXT6.LVDS_P1") (class "Default")
      (node (ref "IC4") (pin "H17") (pinfunction "IO_L6P_T0_15_H17") (pintype "bidirectional"))
    )
    (net (code "151") (name "/EXT6.LVDS_P2") (class "Default")
      (node (ref "IC4") (pin "H20") (pinfunction "IO_L8P_T1_AD10P_15_H20") (pintype "bidirectional"))
    )
    (net (code "152") (name "/EXT6.LVDS_P3") (class "Default")
      (node (ref "IC4") (pin "K17") (pinfunction "IO_L21P_T3_DQS_15_K17") (pintype "bidirectional"))
    )
    (net (code "153") (name "/EXT6.LVDS_P4") (class "Default")
      (node (ref "IC4") (pin "J14") (pinfunction "IO_L3P_T0_DQS_AD1P_15_J14") (pintype "bidirectional"))
    )
    (net (code "154") (name "/EXT6.LVDS_P5") (class "Default")
      (node (ref "IC4") (pin "J22") (pinfunction "IO_L7P_T1_AD2P_15_J22") (pintype "bidirectional"))
    )
    (net (code "155") (name "/EXT6.LVDS_P6") (class "Default")
      (node (ref "IC4") (pin "H13") (pinfunction "IO_L1P_T0_AD0P_15_H13") (pintype "bidirectional"))
    )
    (net (code "156") (name "/EXT6.LVDS_P7") (class "Default")
      (node (ref "IC4") (pin "G15") (pinfunction "IO_L2P_T0_AD8P_15_G15") (pintype "bidirectional"))
    )
    (net (code "159") (name "/EXT7.LVDS_N0") (class "Default")
      (node (ref "IC4") (pin "D19") (pinfunction "IO_L14N_T2_SRCC_16_D19") (pintype "bidirectional"))
    )
    (net (code "160") (name "/EXT7.LVDS_N1") (class "Default")
      (node (ref "IC4") (pin "G22") (pinfunction "IO_L24N_T3_16_G22") (pintype "bidirectional"))
    )
    (net (code "161") (name "/EXT7.LVDS_N2") (class "Default")
      (node (ref "IC4") (pin "F20") (pinfunction "IO_L18N_T2_16_F20") (pintype "bidirectional"))
    )
    (net (code "162") (name "/EXT7.LVDS_N3") (class "Default")
      (node (ref "IC4") (pin "F14") (pinfunction "IO_L1N_T0_16_F14") (pintype "bidirectional"))
    )
    (net (code "163") (name "/EXT7.LVDS_N4") (class "Default")
      (node (ref "IC4") (pin "E14") (pinfunction "IO_L4N_T0_16_E14") (pintype "bidirectional"))
    )
    (net (code "164") (name "/EXT7.LVDS_N5") (class "Default")
      (node (ref "IC4") (pin "D15") (pinfunction "IO_L6N_T0_VREF_16_D15") (pintype "bidirectional"))
    )
    (net (code "165") (name "/EXT7.LVDS_N6") (class "Default")
      (node (ref "IC4") (pin "E18") (pinfunction "IO_L15N_T2_DQS_16_E18") (pintype "bidirectional"))
    )
    (net (code "166") (name "/EXT7.LVDS_N7") (class "Default")
      (node (ref "IC4") (pin "E17") (pinfunction "IO_L2N_T0_16_E17") (pintype "bidirectional"))
    )
    (net (code "168") (name "/EXT7.LVDS_P0") (class "Default")
      (node (ref "IC4") (pin "E19") (pinfunction "IO_L14P_T2_SRCC_16_E19") (pintype "bidirectional"))
    )
    (net (code "169") (name "/EXT7.LVDS_P1") (class "Default")
      (node (ref "IC4") (pin "G21") (pinfunction "IO_L24P_T3_16_G21") (pintype "bidirectional"))
    )
    (net (code "170") (name "/EXT7.LVDS_P2") (class "Default")
      (node (ref "IC4") (pin "F19") (pinfunction "IO_L18P_T2_16_F19") (pintype "bidirectional"))
    )
    (net (code "171") (name "/EXT7.LVDS_P3") (class "Default")
      (node (ref "IC4") (pin "F13") (pinfunction "IO_L1P_T0_16_F13") (pintype "bidirectional"))
    )
    (net (code "172") (name "/EXT7.LVDS_P4") (class "Default")
      (node (ref "IC4") (pin "E13") (pinfunction "IO_L4P_T0_16_E13") (pintype "bidirectional"))
    )
    (net (code "173") (name "/EXT7.LVDS_P5") (class "Default")
      (node (ref "IC4") (pin "D14") (pinfunction "IO_L6P_T0_16_D14") (pintype "bidirectional"))
    )
    (net (code "174") (name "/EXT7.LVDS_P6") (class "Default")
      (node (ref "IC4") (pin "F18") (pinfunction "IO_L15P_T2_DQS_16_F18") (pintype "bidirectional"))
    )
    (net (code "175") (name "/EXT7.LVDS_P7") (class "Default")
      (node (ref "IC4") (pin "F16") (pinfunction "IO_L2P_T0_16_F16") (pintype "bidirectional"))
    )
    (net (code "178") (name "/EXT8.LVDS_N0") (class "Default")
      (node (ref "IC4") (pin "C17") (pinfunction "IO_L12N_T1_MRCC_16_C17") (pintype "bidirectional"))
    )
    (net (code "179") (name "/EXT8.LVDS_N1") (class "Default")
      (node (ref "IC4") (pin "A16") (pinfunction "IO_L9N_T1_DQS_16_A16") (pintype "bidirectional"))
    )
    (net (code "180") (name "/EXT8.LVDS_N2") (class "Default")
      (node (ref "IC4") (pin "A19") (pinfunction "IO_L17N_T2_16_A19") (pintype "bidirectional"))
    )
    (net (code "181") (name "/EXT8.LVDS_N3") (class "Default")
      (node (ref "IC4") (pin "B13") (pinfunction "IO_L8N_T1_16_B13") (pintype "bidirectional"))
    )
    (net (code "182") (name "/EXT8.LVDS_N4") (class "Default")
      (node (ref "IC4") (pin "C15") (pinfunction "IO_L3N_T0_DQS_16_C15") (pintype "bidirectional"))
    )
    (net (code "183") (name "/EXT8.LVDS_N5") (class "Default")
      (node (ref "IC4") (pin "D16") (pinfunction "IO_L5N_T0_16_D16") (pintype "bidirectional"))
    )
    (net (code "184") (name "/EXT8.LVDS_N6") (class "Default")
      (node (ref "IC4") (pin "A21") (pinfunction "IO_L21N_T3_DQS_16_A21") (pintype "bidirectional"))
    )
    (net (code "185") (name "/EXT8.LVDS_N7") (class "Default")
      (node (ref "IC4") (pin "D22") (pinfunction "IO_L22N_T3_16_D22") (pintype "bidirectional"))
    )
    (net (code "187") (name "/EXT8.LVDS_P0") (class "Default")
      (node (ref "IC4") (pin "D17") (pinfunction "IO_L12P_T1_MRCC_16_D17") (pintype "bidirectional"))
    )
    (net (code "188") (name "/EXT8.LVDS_P1") (class "Default")
      (node (ref "IC4") (pin "A15") (pinfunction "IO_L9P_T1_DQS_16_A15") (pintype "bidirectional"))
    )
    (net (code "189") (name "/EXT8.LVDS_P2") (class "Default")
      (node (ref "IC4") (pin "A18") (pinfunction "IO_L17P_T2_16_A18") (pintype "bidirectional"))
    )
    (net (code "190") (name "/EXT8.LVDS_P3") (class "Default")
      (node (ref "IC4") (pin "C13") (pinfunction "IO_L8P_T1_16_C13") (pintype "bidirectional"))
    )
    (net (code "191") (name "/EXT8.LVDS_P4") (class "Default")
      (node (ref "IC4") (pin "C14") (pinfunction "IO_L3P_T0_DQS_16_C14") (pintype "bidirectional"))
    )
    (net (code "192") (name "/EXT8.LVDS_P5") (class "Default")
      (node (ref "IC4") (pin "E16") (pinfunction "IO_L5P_T0_16_E16") (pintype "bidirectional"))
    )
    (net (code "193") (name "/EXT8.LVDS_P6") (class "Default")
      (node (ref "IC4") (pin "B21") (pinfunction "IO_L21P_T3_DQS_16_B21") (pintype "bidirectional"))
    )
    (net (code "194") (name "/EXT8.LVDS_P7") (class "Default")
      (node (ref "IC4") (pin "E22") (pinfunction "IO_L22P_T3_16_E22") (pintype "bidirectional"))
    )
    (net (code "197") (name "/EXT9.LVDS_N0") (class "Default")
      (node (ref "IC4") (pin "C19") (pinfunction "IO_L13N_T2_MRCC_16_C19") (pintype "bidirectional"))
    )
    (net (code "198") (name "/EXT9.LVDS_N1") (class "Default")
      (node (ref "IC4") (pin "A14") (pinfunction "IO_L10N_T1_16_A14") (pintype "bidirectional"))
    )
    (net (code "199") (name "/EXT9.LVDS_N2") (class "Default")
      (node (ref "IC4") (pin "A20") (pinfunction "IO_L16N_T2_16_A20") (pintype "bidirectional"))
    )
    (net (code "200") (name "/EXT9.LVDS_N3") (class "Default")
      (node (ref "IC4") (pin "B16") (pinfunction "IO_L7N_T1_16_B16") (pintype "bidirectional"))
    )
    (net (code "201") (name "/EXT9.LVDS_N4") (class "Default")
      (node (ref "IC4") (pin "C20") (pinfunction "IO_L19N_T3_VREF_16_C20") (pintype "bidirectional"))
    )
    (net (code "202") (name "/EXT9.LVDS_N5") (class "Default")
      (node (ref "IC4") (pin "B18") (pinfunction "IO_L11N_T1_SRCC_16_B18") (pintype "bidirectional"))
    )
    (net (code "203") (name "/EXT9.LVDS_N6") (class "Default")
      (node (ref "IC4") (pin "B22") (pinfunction "IO_L20N_T3_16_B22") (pintype "bidirectional"))
    )
    (net (code "204") (name "/EXT9.LVDS_N7") (class "Default")
      (node (ref "IC4") (pin "D21") (pinfunction "IO_L23N_T3_16_D21") (pintype "bidirectional"))
    )
    (net (code "206") (name "/EXT9.LVDS_P0") (class "Default")
      (node (ref "IC4") (pin "C18") (pinfunction "IO_L13P_T2_MRCC_16_C18") (pintype "bidirectional"))
    )
    (net (code "207") (name "/EXT9.LVDS_P1") (class "Default")
      (node (ref "IC4") (pin "A13") (pinfunction "IO_L10P_T1_16_A13") (pintype "bidirectional"))
    )
    (net (code "208") (name "/EXT9.LVDS_P2") (class "Default")
      (node (ref "IC4") (pin "B20") (pinfunction "IO_L16P_T2_16_B20") (pintype "bidirectional"))
    )
    (net (code "209") (name "/EXT9.LVDS_P3") (class "Default")
      (node (ref "IC4") (pin "B15") (pinfunction "IO_L7P_T1_16_B15") (pintype "bidirectional"))
    )
    (net (code "210") (name "/EXT9.LVDS_P4") (class "Default")
      (node (ref "IC4") (pin "D20") (pinfunction "IO_L19P_T3_16_D20") (pintype "bidirectional"))
    )
    (net (code "211") (name "/EXT9.LVDS_P5") (class "Default")
      (node (ref "IC4") (pin "B17") (pinfunction "IO_L11P_T1_SRCC_16_B17") (pintype "bidirectional"))
    )
    (net (code "212") (name "/EXT9.LVDS_P6") (class "Default")
      (node (ref "IC4") (pin "C22") (pinfunction "IO_L20P_T3_16_C22") (pintype "bidirectional"))
    )
    (net (code "213") (name "/EXT9.LVDS_P7") (class "Default")
      (node (ref "IC4") (pin "E21") (pinfunction "IO_L23P_T3_16_E21") (pintype "bidirectional"))
    )
    (net (code "216") (name "/EXT10.LVDS_N0") (class "Default")
      (node (ref "IC4") (pin "V15") (pinfunction "IO_L14N_T2_SRCC_13_V15") (pintype "bidirectional"))
    )
    (net (code "217") (name "/EXT10.LVDS_N1") (class "Default")
      (node (ref "IC4") (pin "AA16") (pinfunction "IO_L1N_T0_13_AA16") (pintype "bidirectional"))
    )
    (net (code "218") (name "/EXT10.LVDS_N2") (class "Default")
      (node (ref "IC4") (pin "AB17") (pinfunction "IO_L2N_T0_13_AB17") (pintype "bidirectional"))
    )
    (net (code "219") (name "/EXT10.LVDS_N3") (class "Default")
      (node (ref "IC4") (pin "AB15") (pinfunction "IO_L4N_T0_13_AB15") (pintype "bidirectional"))
    )
    (net (code "220") (name "/EXT10.LVDS_N4") (class "Default")
      (node (ref "IC4") (pin "AA14") (pinfunction "IO_L5N_T0_13_AA14") (pintype "bidirectional"))
    )
    (net (code "221") (name "/EXT10.LVDS_N5") (class "Default")
      (node (ref "IC4") (pin "AB13") (pinfunction "IO_L3N_T0_DQS_13_AB13") (pintype "bidirectional"))
    )
    (net (code "222") (name "/EXT10.LVDS_N6") (class "Default")
      (node (ref "IC4") (pin "W12") (pinfunction "IO_L12N_T1_MRCC_13_W12") (pintype "bidirectional"))
    )
    (net (code "223") (name "/EXT10.LVDS_N7") (class "Default")
      (node (ref "IC4") (pin "AB12") (pinfunction "IO_L7N_T1_13_AB12") (pintype "bidirectional"))
    )
    (net (code "225") (name "/EXT10.LVDS_P0") (class "Default")
      (node (ref "IC4") (pin "U15") (pinfunction "IO_L14P_T2_SRCC_13_U15") (pintype "bidirectional"))
    )
    (net (code "226") (name "/EXT10.LVDS_P1") (class "Default")
      (node (ref "IC4") (pin "Y16") (pinfunction "IO_L1P_T0_13_Y16") (pintype "bidirectional"))
    )
    (net (code "227") (name "/EXT10.LVDS_P2") (class "Default")
      (node (ref "IC4") (pin "AB16") (pinfunction "IO_L2P_T0_13_AB16") (pintype "bidirectional"))
    )
    (net (code "228") (name "/EXT10.LVDS_P3") (class "Default")
      (node (ref "IC4") (pin "AA15") (pinfunction "IO_L4P_T0_13_AA15") (pintype "bidirectional"))
    )
    (net (code "229") (name "/EXT10.LVDS_P4") (class "Default")
      (node (ref "IC4") (pin "Y13") (pinfunction "IO_L5P_T0_13_Y13") (pintype "bidirectional"))
    )
    (net (code "230") (name "/EXT10.LVDS_P5") (class "Default")
      (node (ref "IC4") (pin "AA13") (pinfunction "IO_L3P_T0_DQS_13_AA13") (pintype "bidirectional"))
    )
    (net (code "231") (name "/EXT10.LVDS_P6") (class "Default")
      (node (ref "IC4") (pin "W11") (pinfunction "IO_L12P_T1_MRCC_13_W11") (pintype "bidirectional"))
    )
    (net (code "232") (name "/EXT10.LVDS_P7") (class "Default")
      (node (ref "IC4") (pin "AB11") (pinfunction "IO_L7P_T1_13_AB11") (pintype "bidirectional"))
    )
    (net (code "235") (name "/EXT11.LVDS_N0") (class "Default")
      (node (ref "IC4") (pin "Y12") (pinfunction "IO_L11N_T1_SRCC_13_Y12") (pintype "bidirectional"))
    )
    (net (code "236") (name "/EXT11.LVDS_N1") (class "Default")
      (node (ref "IC4") (pin "T15") (pinfunction "IO_L15N_T2_DQS_13_T15") (pintype "bidirectional"))
    )
    (net (code "237") (name "/EXT11.LVDS_N2") (class "Default")
      (node (ref "IC4") (pin "W16") (pinfunction "IO_L16N_T2_13_W16") (pintype "bidirectional"))
    )
    (net (code "238") (name "/EXT11.LVDS_N3") (class "Default")
      (node (ref "IC4") (pin "Y14") (pinfunction "IO_L6N_T0_VREF_13_Y14") (pintype "bidirectional"))
    )
    (net (code "239") (name "/EXT11.LVDS_N4") (class "Default")
      (node (ref "IC4") (pin "V14") (pinfunction "IO_L13N_T2_MRCC_13_V14") (pintype "bidirectional"))
    )
    (net (code "240") (name "/EXT11.LVDS_N5") (class "Default")
      (node (ref "IC4") (pin "W10") (pinfunction "IO_L10N_T1_13_W10") (pintype "bidirectional"))
    )
    (net (code "241") (name "/EXT11.LVDS_N6") (class "Default")
      (node (ref "IC4") (pin "AA11") (pinfunction "IO_L9N_T1_DQS_13_AA11") (pintype "bidirectional"))
    )
    (net (code "242") (name "/EXT11.LVDS_N7") (class "Default")
      (node (ref "IC4") (pin "AB10") (pinfunction "IO_L8N_T1_13_AB10") (pintype "bidirectional"))
    )
    (net (code "244") (name "/EXT11.LVDS_P0") (class "Default")
      (node (ref "IC4") (pin "Y11") (pinfunction "IO_L11P_T1_SRCC_13_Y11") (pintype "bidirectional"))
    )
    (net (code "245") (name "/EXT11.LVDS_P1") (class "Default")
      (node (ref "IC4") (pin "T14") (pinfunction "IO_L15P_T2_DQS_13_T14") (pintype "bidirectional"))
    )
    (net (code "246") (name "/EXT11.LVDS_P2") (class "Default")
      (node (ref "IC4") (pin "W15") (pinfunction "IO_L16P_T2_13_W15") (pintype "bidirectional"))
    )
    (net (code "247") (name "/EXT11.LVDS_P3") (class "Default")
      (node (ref "IC4") (pin "W14") (pinfunction "IO_L6P_T0_13_W14") (pintype "bidirectional"))
    )
    (net (code "248") (name "/EXT11.LVDS_P4") (class "Default")
      (node (ref "IC4") (pin "V13") (pinfunction "IO_L13P_T2_MRCC_13_V13") (pintype "bidirectional"))
    )
    (net (code "249") (name "/EXT11.LVDS_P5") (class "Default")
      (node (ref "IC4") (pin "V10") (pinfunction "IO_L10P_T1_13_V10") (pintype "bidirectional"))
    )
    (net (code "250") (name "/EXT11.LVDS_P6") (class "Default")
      (node (ref "IC4") (pin "AA10") (pinfunction "IO_L9P_T1_DQS_13_AA10") (pintype "bidirectional"))
    )
    (net (code "251") (name "/EXT11.LVDS_P7") (class "Default")
      (node (ref "IC4") (pin "AA9") (pinfunction "IO_L8P_T1_13_AA9") (pintype "bidirectional"))
    )
    (net (code "254") (name "/FAN_PWM") (class "Default")
      (node (ref "C159") (pin "2") (pinfunction "2_2") (pintype "passive"))
      (node (ref "IC4") (pin "N17") (pinfunction "IO_L21P_T3_DQS_14_N17") (pintype "bidirectional"))
    )
    (net (code "255") (name "/FPGA_TESTPOINT0") (class "Default")
      (node (ref "IC4") (pin "T21") (pinfunction "IO_L4P_T0_D04_14_T21") (pintype "bidirectional"))
      (node (ref "TP26") (pin "1") (pinfunction "1_1") (pintype "bidirectional"))
    )
    (net (code "256") (name "/GPIO_INT0") (class "Default")
      (node (ref "IC4") (pin "U18") (pinfunction "IO_L18N_T2_A11_D27_14_U18") (pintype "bidirectional"))
    )
    (net (code "257") (name "/GPIO_INT1") (class "Default")
      (node (ref "IC4") (pin "R17") (pinfunction "IO_L24N_T3_A00_D16_14_R17") (pintype "bidirectional"))
    )
    (net (code "259") (name "/HW_REV0") (class "Default")
      (node (ref "IC4") (pin "T16") (pinfunction "IO_L17P_T2_13_T16") (pintype "bidirectional"))
    )
    (net (code "260") (name "/HW_REV1") (class "Default")
      (node (ref "IC4") (pin "U16") (pinfunction "IO_L17N_T2_13_U16") (pintype "bidirectional"))
    )
    (net (code "261") (name "/HW_REV2") (class "Default")
      (node (ref "IC4") (pin "T3") (pinfunction "IO_0_34_T3") (pintype "bidirectional"))
    )
    (net (code "262") (name "/HW_REV3") (class "Default")
      (node (ref "IC4") (pin "F21") (pinfunction "IO_25_16_F21") (pintype "bidirectional"))
    )
    (net (code "263") (name "/Helper_DCXO_N") (class "Default")
      (node (ref "IC4") (pin "W20") (pinfunction "IO_L12N_T1_MRCC_14_W20") (pintype "bidirectional"))
    )
    (net (code "264") (name "/Helper_DCXO_P") (class "Default")
      (node (ref "IC4") (pin "W19") (pinfunction "IO_L12P_T1_MRCC_14_W19") (pintype "bidirectional"))
    )
    (net (code "265") (name "/Helper_DCXO_SCL") (class "Default")
      (node (ref "IC4") (pin "N13") (pinfunction "IO_L23P_T3_A03_D19_14_N13") (pintype "bidirectional"))
    )
    (net (code "266") (name "/Helper_DCXO_SDA") (class "Default")
      (node (ref "IC4") (pin "N15") (pinfunction "IO_25_14_N15") (pintype "bidirectional"))
    )
    (net (code "267") (name "/I2C_SW_RESET") (class "Default")
      (node (ref "IC4") (pin "U17") (pinfunction "IO_L18P_T2_A12_D28_14_U17") (pintype "bidirectional"))
    )
    (net (code "268") (name "/I2C_SW_SCL") (class "Default")
      (node (ref "IC4") (pin "J16") (pinfunction "IO_0_15_J16") (pintype "bidirectional"))
    )
    (net (code "269") (name "/I2C_SW_SDA") (class "Default")
      (node (ref "IC4") (pin "M17") (pinfunction "IO_25_15_M17") (pintype "bidirectional"))
    )
    (net (code "270") (name "/LED_ERR") (class "Default")
      (node (ref "IC4") (pin "F15") (pinfunction "IO_0_16_F15") (pintype "bidirectional"))
      (node (ref "R23") (pin "2") (pinfunction "2_2") (pintype "passive"))
      (node (ref "T12") (pin "1") (pinfunction "G_1") (pintype "passive"))
    )
    (net (code "271") (name "/LED_USER0") (class "Default")
      (node (ref "IC4") (pin "P14") (pinfunction "IO_L19P_T3_A10_D26_14_P14") (pintype "bidirectional"))
      (node (ref "R45") (pin "2") (pinfunction "2_2") (pintype "passive"))
      (node (ref "T3") (pin "1") (pinfunction "G_1") (pintype "passive"))
    )
    (net (code "272") (name "/LED_USER1") (class "Default")
      (node (ref "IC4") (pin "R19") (pinfunction "IO_L5N_T0_D07_14_R19") (pintype "bidirectional"))
      (node (ref "R227") (pin "2") (pinfunction "2_2") (pintype "passive"))
      (node (ref "T19") (pin "1") (pinfunction "G_1") (pintype "passive"))
    )
    (net (code "273") (name "/LED_USER2") (class "Default")
      (node (ref "IC4") (pin "R16") (pinfunction "IO_L22N_T3_A04_D20_14_R16") (pintype "bidirectional"))
      (node (ref "R19") (pin "2") (pinfunction "2_2") (pintype "passive"))
      (node (ref "T2") (pin "1") (pinfunction "G_1") (pintype "passive"))
    )
    (net (code "274") (name "/Main_DCXO_SCL") (class "Default")
      (node (ref "IC4") (pin "U7") (pinfunction "IO_25_34_U7") (pintype "bidirectional"))
    )
    (net (code "275") (name "/Main_DCXO_SDA") (class "Default")
      (node (ref "IC4") (pin "N14") (pinfunction "IO_L23N_T3_A02_D18_14_N14") (pintype "bidirectional"))
    )
    (net (code "276") (name "/P3V3_EN") (class "Default")
      (node (ref "NT1") (pin "2") (pinfunction "2_2") (pintype "bidirectional"))
    )
    (net (code "277") (name "/P3V3_FLT_N") (class "Default")
      (node (ref "NT2") (pin "2") (pinfunction "2_2") (pintype "bidirectional"))
    )
    (net (code "278") (name "/RxD_2V5") (class "Default")
      (node (ref "IC4") (pin "P17") (pinfunction "IO_L21N_T3_DQS_A06_D22_14_P17") (pintype "bidirectional"))
    )
    (net (code "279") (name "/TxD_2V5") (class "Default")
      (node (ref "IC4") (pin "P16") (pinfunction "IO_L24P_T3_A01_D17_14_P16") (pintype "bidirectional"))
    )
    (net (code "291") (name "GND") (class "Default")
      (node (ref "R19") (pin "1") (pinfunction "1_1") (pintype "passive"))
      (node (ref "R227") (pin "1") (pinfunction "1_1") (pintype "passive"))
      (node (ref "R23") (pin "1") (pinfunction "1_1") (pintype "passive"))
      (node (ref "R43") (pin "1") (pinfunction "1_1") (pintype "passive"))
      (node (ref "R45") (pin "1") (pinfunction "1_1") (pintype "passive"))
      (node (ref "R9") (pin "1") (pinfunction "1_1") (pintype "passive"))
      (node (ref "SW1") (pin "2") (pinfunction "2_2") (pintype "bidirectional"))
      (node (ref "T12") (pin "2") (pinfunction "S_2") (pintype "passive"))
      (node (ref "T19") (pin "2") (pinfunction "S_2") (pintype "passive"))
      (node (ref "T2") (pin "2") (pinfunction "S_2") (pintype "passive"))
      (node (ref "T20") (pin "2") (pinfunction "S_2") (pintype "passive"))
      (node (ref "T3") (pin "2") (pinfunction "S_2") (pintype "passive"))
      (node (ref "TP28") (pin "1") (pinfunction "1_1") (pintype "bidirectional"))
      (node (ref "TP33") (pin "1") (pinfunction "1_1") (pintype "bidirectional"))
    )
    (net (code "292") (name "Net-(D17-A)") (class "Default")
      (node (ref "C159") (pin "1") (pinfunction "1_1") (pintype "passive"))
      (node (ref "D17") (pin "2") (pinfunction "A_2") (pintype "passive"))
      (node (ref "R150") (pin "1") (pinfunction "1_1") (pintype "passive"))
      (node (ref "T20") (pin "1") (pinfunction "G_1") (pintype "passive"))
    )
    (net (code "293") (name "Net-(D18-A)") (class "Default")
      (node (ref "D18") (pin "2") (pinfunction "A_2") (pintype "passive"))
      (node (ref "J21") (pin "1") (pinfunction "1_1") (pintype "bidirectional"))
      (node (ref "T20") (pin "3") (pinfunction "D_3") (pintype "passive"))
    )
    (net (code "294") (name "Net-(LD2-A)") (class "Default")
      (node (ref "LD2") (pin "2") (pinfunction "A_2") (pintype "passive"))
      (node (ref "R44") (pin "1") (pinfunction "1_1") (pintype "passive"))
    )
    (net (code "295") (name "Net-(LD2-C)") (class "Default")
      (node (ref "LD2") (pin "1") (pinfunction "C_1") (pintype "passive"))
      (node (ref "T3") (pin "3") (pinfunction "D_3") (pintype "passive"))
    )
    (net (code "296") (name "Net-(LD13-A)") (class "Default")
      (node (ref "LD13") (pin "2") (pinfunction "A_2") (pintype "passive"))
      (node (ref "R11") (pin "1") (pinfunction "1_1") (pintype "passive"))
    )
    (net (code "297") (name "Net-(LD13-C)") (class "Default")
      (node (ref "LD13") (pin "1") (pinfunction "C_1") (pintype "passive"))
      (node (ref "T2") (pin "3") (pinfunction "D_3") (pintype "passive"))
    )
    (net (code "298") (name "Net-(LD14-A)") (class "Default")
      (node (ref "LD14") (pin "2") (pinfunction "A_2") (pintype "passive"))
      (node (ref "R20") (pin "1") (pinfunction "1_1") (pintype "passive"))
    )
    (net (code "299") (name "Net-(LD14-C)") (class "Default")
      (node (ref "LD14") (pin "1") (pinfunction "C_1") (pintype "passive"))
      (node (ref "T12") (pin "3") (pinfunction "D_3") (pintype "passive"))
    )
    (net (code "300") (name "Net-(LD18-A)") (class "Default")
      (node (ref "LD18") (pin "2") (pinfunction "A_2") (pintype "passive"))
      (node (ref "R226") (pin "1") (pinfunction "1_1") (pintype "passive"))
    )
    (net (code "301") (name "Net-(LD18-C)") (class "Default")
      (node (ref "LD18") (pin "1") (pinfunction "C_1") (pintype "passive"))
      (node (ref "T19") (pin "3") (pinfunction "D_3") (pintype "passive"))
    )
    (net (code "302") (name "P2V5") (class "Default")
      (node (ref "D17") (pin "1") (pinfunction "C_1") (pintype "passive"))
      (node (ref "R150") (pin "2") (pinfunction "2_2") (pintype "passive"))
      (node (ref "R258") (pin "2") (pinfunction "2_2") (pintype "passive"))
      (node (ref "R42") (pin "2") (pinfunction "2_2") (pintype "passive"))
      (node (ref "TP32") (pin "1") (pinfunction "1_1") (pintype "bidirectional"))
    )
    (net (code "303") (name "P3V3") (class "Default")
      (node (ref "R11") (pin "2") (pinfunction "2_2") (pintype "passive"))
      (node (ref "R20") (pin "2") (pinfunction "2_2") (pintype "passive"))
      (node (ref "R226") (pin "2") (pinfunction "2_2") (pintype "passive"))
      (node (ref "R44") (pin "2") (pinfunction "2_2") (pintype "passive"))
      (node (ref "TP31") (pin "1") (pinfunction "1_1") (pintype "bidirectional"))
    )
    (net (code "304") (name "P12V0_SMPS") (class "Default")
      (node (ref "D18") (pin "1") (pinfunction "C_1") (pintype "passive"))
      (node (ref "J21") (pin "2") (pinfunction "2_2") (pintype "bidirectional"))
    )
    (net (code "305") (name "unconnected-(IC4A-IO_0_13-PadY17)") (class "Default")
      (node (ref "IC4") (pin "Y17") (pinfunction "IO_0_13_Y17") (pintype "bidirectional+no_connect"))
    )
    (net (code "306") (name "unconnected-(IC4B-IO_L19N_T3_A09_D25_VREF_14-PadR14)") (class "Default")
      (node (ref "IC4") (pin "R14") (pinfunction "IO_L19N_T3_A09_D25_VREF_14_R14") (pintype "bidirectional+no_connect"))
    )
  )
)
